# PROC099A_CAN_Interface.net
KiCad netlist of a schematic drawn in Altium Designer
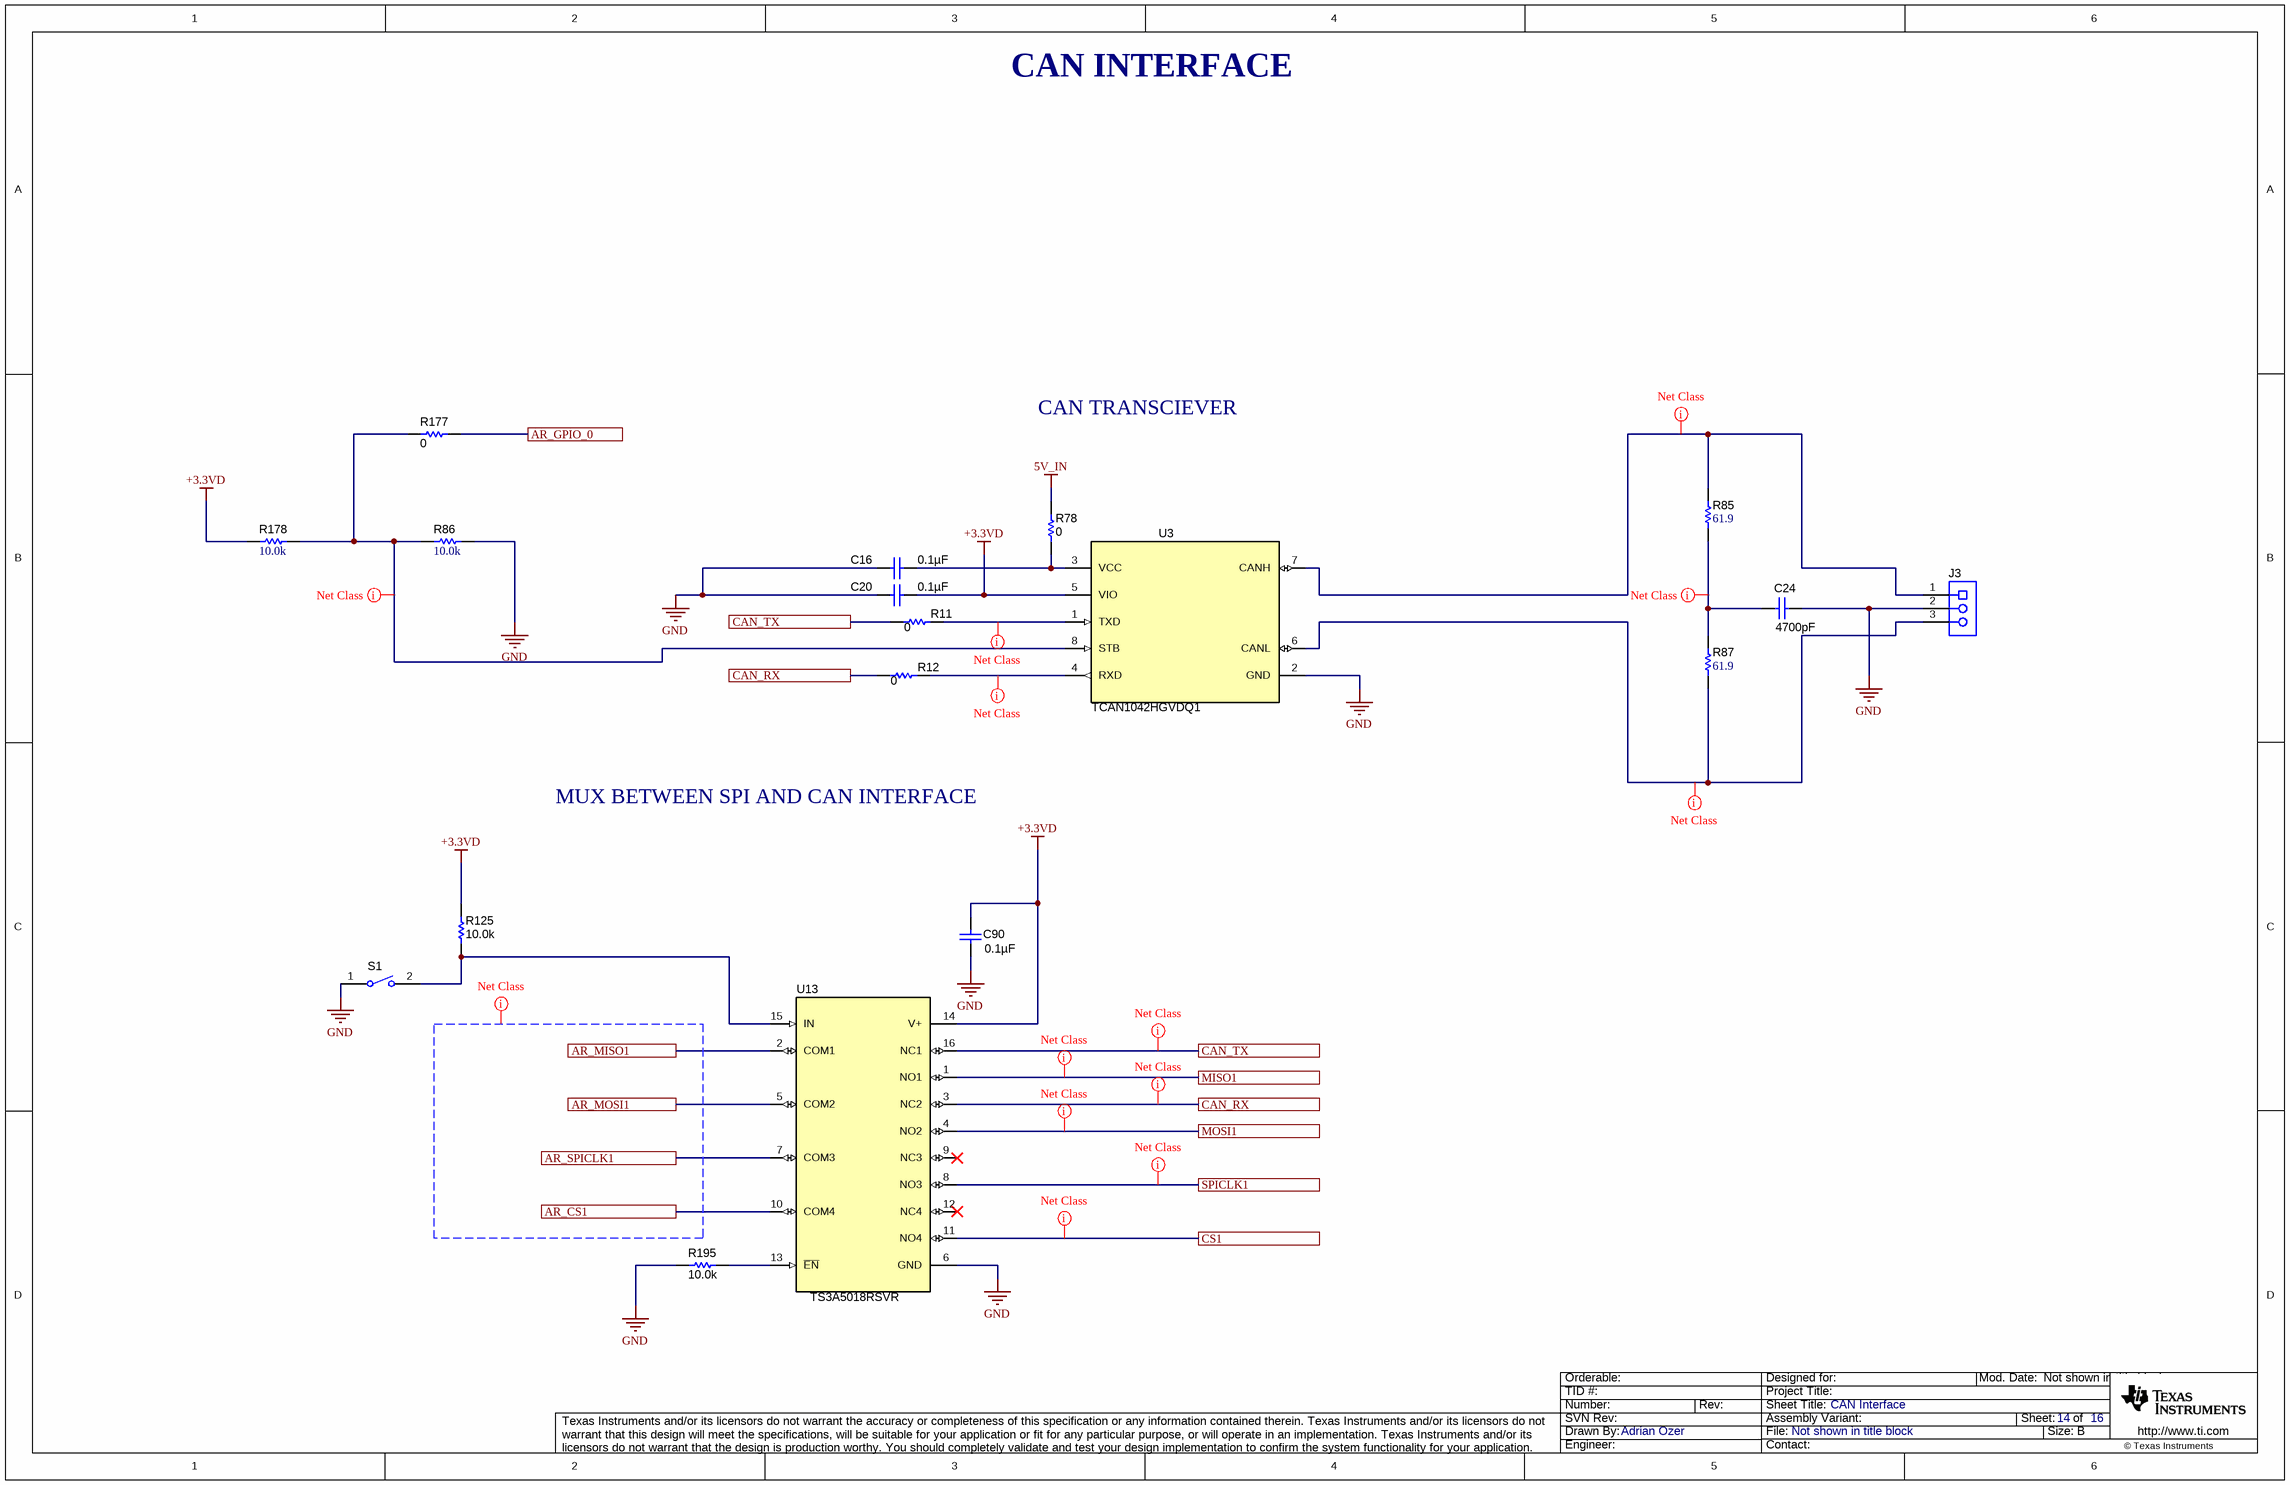
[diagram p0: PROC099A_CAN Interface.SchDoc]

(export (version "E")
  (design (tool "Eeschema 10.0.6"))
  (components
    (comp (ref "C16")
      (value "C0402C104K8RACTU")
      (footprint "0402L")
      (description "CAP, CERM, 0.1 µF, 10 V,+/- 10%, X7R, 0402")
      (fields (field (name "MANUFACTURER") "Kemet") (field (name "VALUEDISPLAYED") "0.1µF"))
      (libsource (lib "Altium Vault - TI") (part "Capacitor"))
    )
    (comp (ref "C20")
      (value "C0402C104K8RACTU")
      (footprint "0402L")
      (description "CAP, CERM, 0.1 µF, 10 V,+/- 10%, X7R, 0402")
      (fields (field (name "MANUFACTURER") "Kemet") (field (name "VALUEDISPLAYED") "0.1µF"))
      (libsource (lib "Altium Vault - TI") (part "Capacitor"))
    )
    (comp (ref "C24")
      (value "GCM155R71H472KA37D")
      (footprint "0402S")
      (description "CAP, CERM, 4700 pF, 50 V, +/- 10%, X7R, AEC-Q200 Grade 1, 0402")
      (fields
        (field (name "MANUFACTURER") "MuRata")
        (field (name "VALUEDISPLAYED") "4700pF")
        (field (name "PUBLISHER") "Texas Instruments")
      )
      (libsource (lib "Altium Vault - TI") (part "Capacitor"))
    )
    (comp (ref "C90")
      (value "C0402C104K8RACTU")
      (footprint "0402L")
      (description "CAP, CERM, 0.1 µF, 10 V,+/- 10%, X7R, 0402")
      (fields (field (name "MANUFACTURER") "Kemet") (field (name "VALUEDISPLAYED") "0.1µF"))
      (libsource (lib "Altium Vault - TI") (part "Capacitor"))
    )
    (comp (ref "J3")
      (value "OSTTE030161")
      (footprint "On-Shore_OSTTE030161")
      (description "Terminal Block, 3.5mm, 3x1, Tin, R/A, TH")
      (fields
        (field (name "MANUFACTURER") "On-Shore Technology")
        (field (name "PUBLISHER") "Texas Instruments")
      )
      (libsource (lib "Altium Vault - TI") (part "Receptacle_3x1"))
    )
    (comp (ref "R11")
      (value "ERJ-2GE0R00X")
      (footprint "0402L")
      (description "RES, 0, 5%, 0.063 W, 0402")
      (fields
        (field (name "MANUFACTURER") "Panasonic")
        (field (name "VALUEDISPLAYED") "0")
        (field (name "PUBLISHER") "Texas Instruments")
      )
      (libsource (lib "Altium Vault - TI") (part "CMP-0026992-2"))
    )
    (comp (ref "R12")
      (value "ERJ-2GE0R00X")
      (footprint "0402L")
      (description "RES, 0, 5%, 0.063 W, 0402")
      (fields
        (field (name "MANUFACTURER") "Panasonic")
        (field (name "VALUEDISPLAYED") "0")
        (field (name "PUBLISHER") "Texas Instruments")
      )
      (libsource (lib "Altium Vault - TI") (part "CMP-0026992-2"))
    )
    (comp (ref "R78")
      (value "ERJ-2GE0R00X")
      (footprint "0402L")
      (description "RES, 0, 5%, 0.063 W, 0402")
      (fields
        (field (name "MANUFACTURER") "Panasonic")
        (field (name "VALUEDISPLAYED") "0")
        (field (name "PUBLISHER") "Texas Instruments")
      )
      (libsource (lib "Altium Vault - TI") (part "CMP-0026992-2"))
    )
    (comp (ref "R85")
      (value "CRCW040261R9FKED")
      (footprint "0402L")
      (description "RES, 61.9, 1%, 0.063 W, AEC-Q200 Grade 0, 0402")
      (fields (field (name "MANUFACTURER") "Vishay-Dale") (field (name "VALUEDISPLAYED") "61.9"))
      (libsource (lib "Altium Vault - TI") (part "Resistor"))
    )
    (comp (ref "R86")
      (value "CRCW040210K0FKED")
      (footprint "0402L")
      (description "RES, 10.0 k, 1%, 0.063 W, AEC-Q200 Grade 0, 0402")
      (fields (field (name "MANUFACTURER") "Vishay-Dale") (field (name "VALUEDISPLAYED") "10.0k"))
      (libsource (lib "Altium Vault - TI") (part "Resistor"))
    )
    (comp (ref "R87")
      (value "CRCW040261R9FKED")
      (footprint "0402L")
      (description "RES, 61.9, 1%, 0.063 W, AEC-Q200 Grade 0, 0402")
      (fields (field (name "MANUFACTURER") "Vishay-Dale") (field (name "VALUEDISPLAYED") "61.9"))
      (libsource (lib "Altium Vault - TI") (part "Resistor"))
    )
    (comp (ref "R125")
      (value "CRCW040210K0FKED")
      (footprint "0402L")
      (description "RES, 10.0 k, 1%, 0.063 W, 0402")
      (fields
        (field (name "MANUFACTURER") "Vishay-Dale")
        (field (name "VALUEDISPLAYED") "10.0k")
        (field (name "PUBLISHER") "Texas Instruments")
      )
      (libsource (lib "Altium Vault - TI") (part "CMP-0025958-2"))
    )
    (comp (ref "R177")
      (value "ERJ-2GE0R00X")
      (footprint "0402L")
      (description "RES, 0, 5%, 0.063 W, 0402")
      (fields
        (field (name "MANUFACTURER") "Panasonic")
        (field (name "VALUEDISPLAYED") "0")
        (field (name "PUBLISHER") "Texas Instruments")
      )
      (libsource (lib "Altium Vault - TI") (part "CMP-0026992-2"))
    )
    (comp (ref "R178")
      (value "CRCW040210K0FKED")
      (footprint "0402L")
      (description "RES, 10.0 k, 1%, 0.063 W, AEC-Q200 Grade 0, 0402")
      (fields (field (name "MANUFACTURER") "Vishay-Dale") (field (name "VALUEDISPLAYED") "10.0k"))
      (libsource (lib "Altium Vault - TI") (part "Resistor"))
    )
    (comp (ref "R195")
      (value "CRCW040210K0FKED")
      (footprint "0402L")
      (description "RES, 10.0 k, 1%, 0.063 W, 0402")
      (fields
        (field (name "MANUFACTURER") "Vishay-Dale")
        (field (name "VALUEDISPLAYED") "10.0k")
        (field (name "PUBLISHER") "Texas Instruments")
      )
      (libsource (lib "Altium Vault - TI") (part "CMP-0025958-2"))
    )
    (comp (ref "S1")
      (value "CHS-01TB")
      (footprint "SW_CHS-01TB")
      (description "Switch, Slide, SPST, Top Slide, SMT")
      (fields
        (field (name "MANUFACTURER") "Copal Electronics")
        (field (name "PUBLISHER") "Texas Instruments")
      )
      (libsource (lib "Altium Vault - TI") (part "SW_SPST-single"))
    )
    (comp (ref "U3")
      (value "TCAN1042HGVDQ1")
      (footprint "D0008A_L")
      (description "Automotive Fault Protected CAN Transceiver With Flexible Data-Rate, D0008A (SOIC-8)")
      (fields
        (field (name "PARTNUMBER") "TCAN1042HGVDQ1")
        (field (name "MANUFACTURER") "Texas Instruments")
        (field (name "ALTERNATE PARTNUMBER") "TCAN1042HGVDRQ1")
        (field (name "PUBLISHER") "Texas Instruments")
      )
      (libsource (lib "Altium Vault - TI") (part "TCAN1042_V"))
    )
    (comp (ref "U13")
      (value "TS3A5018RSVR")
      (footprint "RSV0016A")
      (description "10-Ohm Quad SPDT Analog Switch, RSV0016A (UQFN-16)")
      (fields
        (field (name "MANUFACTURER") "Texas Instruments")
        (field (name "PARTNUMBER") "TS3A5018RSVR")
        (field (name "PUBLISHER") "Texas Instruments")
      )
      (libsource (lib "Altium Vault - TI") (part "CMP-0067415-1"))
    )
  )
  (nets
    (net (code "1") (name "+3.3VD") (class "Default")
      (node (ref "C20") (pin "2") (pinfunction "2_2") (pintype "passive"))
      (node (ref "C90") (pin "2") (pinfunction "2_2") (pintype "passive"))
      (node (ref "R125") (pin "2") (pinfunction "2_2") (pintype "passive"))
      (node (ref "R178") (pin "1") (pinfunction "1_1") (pintype "passive"))
      (node (ref "U13") (pin "14") (pinfunction "V+_14") (pintype "power_in"))
      (node (ref "U3") (pin "5") (pinfunction "VIO_5") (pintype "power_in"))
    )
    (net (code "2") (name "/AR_CS1") (class "Default")
      (node (ref "U13") (pin "10") (pinfunction "COM4_10") (pintype "bidirectional"))
    )
    (net (code "3") (name "/AR_GPIO_0") (class "Default")
      (node (ref "R177") (pin "2") (pinfunction "2_2") (pintype "passive"))
    )
    (net (code "4") (name "/AR_MISO1") (class "Default")
      (node (ref "U13") (pin "2") (pinfunction "COM1_2") (pintype "bidirectional"))
    )
    (net (code "5") (name "/AR_MOSI1") (class "Default")
      (node (ref "U13") (pin "5") (pinfunction "COM2_5") (pintype "bidirectional"))
    )
    (net (code "6") (name "/AR_SPICLK1") (class "Default")
      (node (ref "U13") (pin "7") (pinfunction "COM3_7") (pintype "bidirectional"))
    )
    (net (code "7") (name "/CAN_RX") (class "Default")
      (node (ref "R12") (pin "1") (pinfunction "1_1") (pintype "passive"))
      (node (ref "U13") (pin "3") (pinfunction "NC2_3") (pintype "bidirectional"))
    )
    (net (code "8") (name "/CAN_TX") (class "Default")
      (node (ref "R11") (pin "1") (pinfunction "1_1") (pintype "passive"))
      (node (ref "U13") (pin "16") (pinfunction "NC1_16") (pintype "bidirectional"))
    )
    (net (code "9") (name "/CS1") (class "Default")
      (node (ref "U13") (pin "11") (pinfunction "NO4_11") (pintype "bidirectional"))
    )
    (net (code "10") (name "/MISO1") (class "Default")
      (node (ref "U13") (pin "1") (pinfunction "NO1_1") (pintype "bidirectional"))
    )
    (net (code "11") (name "/MOSI1") (class "Default")
      (node (ref "U13") (pin "4") (pinfunction "NO2_4") (pintype "bidirectional"))
    )
    (net (code "12") (name "/SPICLK1") (class "Default")
      (node (ref "U13") (pin "8") (pinfunction "NO3_8") (pintype "bidirectional"))
    )
    (net (code "13") (name "5V_IN") (class "Default")
      (node (ref "R78") (pin "2") (pinfunction "2_2") (pintype "passive"))
    )
    (net (code "14") (name "GND") (class "Default")
      (node (ref "C16") (pin "1") (pinfunction "1_1") (pintype "passive"))
      (node (ref "C20") (pin "1") (pinfunction "1_1") (pintype "passive"))
      (node (ref "C24") (pin "1") (pinfunction "1_1") (pintype "passive"))
      (node (ref "C90") (pin "1") (pinfunction "1_1") (pintype "passive"))
      (node (ref "J3") (pin "2") (pinfunction "2_2") (pintype "passive"))
      (node (ref "R195") (pin "2") (pinfunction "2_2") (pintype "passive"))
      (node (ref "R86") (pin "2") (pinfunction "2_2") (pintype "passive"))
      (node (ref "S1") (pin "1") (pinfunction "1_1") (pintype "passive"))
      (node (ref "U13") (pin "6") (pinfunction "GND_6") (pintype "power_in"))
      (node (ref "U3") (pin "2") (pinfunction "GND_2") (pintype "power_in"))
    )
    (net (code "15") (name "Net-(C24-Pad2)") (class "Default")
      (node (ref "C24") (pin "2") (pinfunction "2_2") (pintype "passive"))
      (node (ref "R85") (pin "1") (pinfunction "1_1") (pintype "passive"))
      (node (ref "R87") (pin "2") (pinfunction "2_2") (pintype "passive"))
    )
    (net (code "16") (name "Net-(U3-CANH)") (class "Default")
      (node (ref "J3") (pin "1") (pinfunction "1_1") (pintype "passive"))
      (node (ref "R85") (pin "2") (pinfunction "2_2") (pintype "passive"))
      (node (ref "U3") (pin "7") (pinfunction "CANH_7") (pintype "bidirectional"))
    )
    (net (code "17") (name "Net-(U3-CANL)") (class "Default")
      (node (ref "J3") (pin "3") (pinfunction "3_3") (pintype "passive"))
      (node (ref "R87") (pin "1") (pinfunction "1_1") (pintype "passive"))
      (node (ref "U3") (pin "6") (pinfunction "CANL_6") (pintype "bidirectional"))
    )
    (net (code "18") (name "Net-(U3-RXD)") (class "Default")
      (node (ref "R12") (pin "2") (pinfunction "2_2") (pintype "passive"))
      (node (ref "U3") (pin "4") (pinfunction "RXD_4") (pintype "output"))
    )
    (net (code "19") (name "Net-(U3-STB)") (class "Default")
      (node (ref "R177") (pin "1") (pinfunction "1_1") (pintype "passive"))
      (node (ref "R178") (pin "2") (pinfunction "2_2") (pintype "passive"))
      (node (ref "R86") (pin "1") (pinfunction "1_1") (pintype "passive"))
      (node (ref "U3") (pin "8") (pinfunction "STB_8") (pintype "input"))
    )
    (net (code "20") (name "Net-(U3-TXD)") (class "Default")
      (node (ref "R11") (pin "2") (pinfunction "2_2") (pintype "passive"))
      (node (ref "U3") (pin "1") (pinfunction "TXD_1") (pintype "input"))
    )
    (net (code "21") (name "Net-(U3-VCC)") (class "Default")
      (node (ref "C16") (pin "2") (pinfunction "2_2") (pintype "passive"))
      (node (ref "R78") (pin "1") (pinfunction "1_1") (pintype "passive"))
      (node (ref "U3") (pin "3") (pinfunction "VCC_3") (pintype "power_in"))
    )
    (net (code "22") (name "Net-(U13-EN)") (class "Default")
      (node (ref "R195") (pin "1") (pinfunction "1_1") (pintype "passive"))
      (node (ref "U13") (pin "13") (pinfunction "EN_13") (pintype "input"))
    )
    (net (code "23") (name "Net-(U13-IN)") (class "Default")
      (node (ref "R125") (pin "1") (pinfunction "1_1") (pintype "passive"))
      (node (ref "S1") (pin "2") (pinfunction "2_2") (pintype "passive"))
      (node (ref "U13") (pin "15") (pinfunction "IN_15") (pintype "input"))
    )
    (net (code "24") (name "unconnected-(U13-NC3-Pad9)") (class "Default")
      (node (ref "U13") (pin "9") (pinfunction "NC3_9") (pintype "bidirectional+no_connect"))
    )
    (net (code "25") (name "unconnected-(U13-NC4-Pad12)") (class "Default")
      (node (ref "U13") (pin "12") (pinfunction "NC4_12") (pintype "bidirectional+no_connect"))
    )
  )
)
